# Side2.net
KiCad netlist of a schematic drawn in Altium Designer
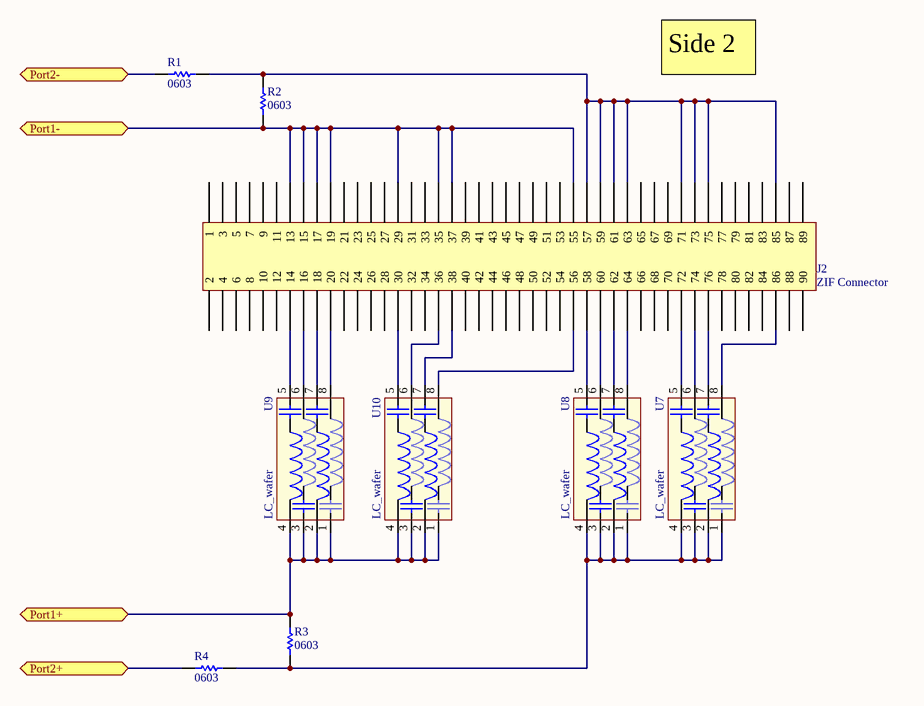
[diagram p0: Side2.SchDoc]

(export (version "E")
  (design (tool "Eeschema 10.0.6"))
  (components
    (comp (ref "J2")
      (value "ZIF Connector")
      (footprint "LCBoard_ZIFCon")
      (libsource (lib "altium-import") (part "root_1_LCboard_FH16-90S-0.3SHW(05)_"))
    )
    (comp (ref "R1")
      (value "0603")
      (footprint "0603")
      (description "RES 1 OHM 1/10W 1% 0603 SMD")
      (libsource (lib "LCboardPCB") (part "Res0603"))
    )
    (comp (ref "R2")
      (value "0603")
      (footprint "0603")
      (description "RES 1 OHM 1/10W 1% 0603 SMD")
      (libsource (lib "LCboardPCB") (part "Res0603"))
    )
    (comp (ref "R3")
      (value "0603")
      (footprint "0603")
      (description "RES 1 OHM 1/10W 1% 0603 SMD")
      (libsource (lib "LCboardPCB") (part "Res0603"))
    )
    (comp (ref "R4")
      (value "0603")
      (footprint "0603")
      (description "RES 1 OHM 1/10W 1% 0603 SMD")
      (libsource (lib "LCboardPCB") (part "Res0603"))
    )
    (comp (ref "U7")
      (value "LC_wafer")
      (footprint "LCWafer")
      (description "Gold bonded integrated LC")
      (libsource (lib "LCboardPCB") (part "LCWafer"))
    )
    (comp (ref "U8")
      (value "LC_wafer")
      (footprint "LCWafer")
      (description "Gold bonded integrated LC")
      (libsource (lib "LCboardPCB") (part "LCWafer"))
    )
    (comp (ref "U9")
      (value "LC_wafer")
      (footprint "LCWafer")
      (description "Gold bonded integrated LC")
      (libsource (lib "LCboardPCB") (part "LCWafer"))
    )
    (comp (ref "U10")
      (value "LC_wafer")
      (footprint "LCWafer")
      (description "Gold bonded integrated LC")
      (libsource (lib "LCboardPCB") (part "LCWafer"))
    )
  )
  (nets
    (net (code "1") (name "/Port1+") (class "Default")
      (node (ref "R3") (pin "2") (pinfunction "2_2") (pintype "passive"))
      (node (ref "U10") (pin "1") (pinfunction "1_1") (pintype "passive"))
      (node (ref "U10") (pin "2") (pinfunction "2_2") (pintype "passive"))
      (node (ref "U10") (pin "3") (pinfunction "3_3") (pintype "passive"))
      (node (ref "U10") (pin "4") (pinfunction "4_4") (pintype "passive"))
      (node (ref "U9") (pin "1") (pinfunction "1_1") (pintype "passive"))
      (node (ref "U9") (pin "2") (pinfunction "2_2") (pintype "passive"))
      (node (ref "U9") (pin "3") (pinfunction "3_3") (pintype "passive"))
      (node (ref "U9") (pin "4") (pinfunction "4_4") (pintype "passive"))
    )
    (net (code "2") (name "/Port1-") (class "Default")
      (node (ref "J2") (pin "13") (pinfunction "13_13") (pintype "passive"))
      (node (ref "J2") (pin "15") (pinfunction "15_15") (pintype "passive"))
      (node (ref "J2") (pin "17") (pinfunction "17_17") (pintype "passive"))
      (node (ref "J2") (pin "19") (pinfunction "19_19") (pintype "passive"))
      (node (ref "J2") (pin "29") (pinfunction "29_29") (pintype "passive"))
      (node (ref "J2") (pin "35") (pinfunction "35_35") (pintype "passive"))
      (node (ref "J2") (pin "37") (pinfunction "37_37") (pintype "passive"))
      (node (ref "J2") (pin "55") (pinfunction "55_55") (pintype "passive"))
      (node (ref "R2") (pin "1") (pinfunction "1_1") (pintype "passive"))
    )
    (net (code "3") (name "/Port2+") (class "Default")
      (node (ref "R4") (pin "2") (pinfunction "2_2") (pintype "passive"))
    )
    (net (code "4") (name "/Port2-") (class "Default")
      (node (ref "R1") (pin "2") (pinfunction "2_2") (pintype "passive"))
    )
    (net (code "5") (name "Net-(J2-Pad14)") (class "Default")
      (node (ref "J2") (pin "14") (pinfunction "14_14") (pintype "passive"))
      (node (ref "U9") (pin "5") (pinfunction "5_5") (pintype "passive"))
    )
    (net (code "6") (name "Net-(J2-Pad16)") (class "Default")
      (node (ref "J2") (pin "16") (pinfunction "16_16") (pintype "passive"))
      (node (ref "U9") (pin "6") (pinfunction "6_6") (pintype "passive"))
    )
    (net (code "7") (name "Net-(J2-Pad18)") (class "Default")
      (node (ref "J2") (pin "18") (pinfunction "18_18") (pintype "passive"))
      (node (ref "U9") (pin "7") (pinfunction "7_7") (pintype "passive"))
    )
    (net (code "8") (name "Net-(J2-Pad20)") (class "Default")
      (node (ref "J2") (pin "20") (pinfunction "20_20") (pintype "passive"))
      (node (ref "U9") (pin "8") (pinfunction "8_8") (pintype "passive"))
    )
    (net (code "9") (name "Net-(J2-Pad30)") (class "Default")
      (node (ref "J2") (pin "30") (pinfunction "30_30") (pintype "passive"))
      (node (ref "U10") (pin "5") (pinfunction "5_5") (pintype "passive"))
    )
    (net (code "10") (name "Net-(J2-Pad36)") (class "Default")
      (node (ref "J2") (pin "36") (pinfunction "36_36") (pintype "passive"))
      (node (ref "U10") (pin "6") (pinfunction "6_6") (pintype "passive"))
    )
    (net (code "11") (name "Net-(J2-Pad38)") (class "Default")
      (node (ref "J2") (pin "38") (pinfunction "38_38") (pintype "passive"))
      (node (ref "U10") (pin "7") (pinfunction "7_7") (pintype "passive"))
    )
    (net (code "12") (name "Net-(J2-Pad56)") (class "Default")
      (node (ref "J2") (pin "56") (pinfunction "56_56") (pintype "passive"))
      (node (ref "U10") (pin "8") (pinfunction "8_8") (pintype "passive"))
    )
    (net (code "13") (name "Net-(J2-Pad57)") (class "Default")
      (node (ref "J2") (pin "57") (pinfunction "57_57") (pintype "passive"))
      (node (ref "J2") (pin "59") (pinfunction "59_59") (pintype "passive"))
      (node (ref "J2") (pin "61") (pinfunction "61_61") (pintype "passive"))
      (node (ref "J2") (pin "63") (pinfunction "63_63") (pintype "passive"))
      (node (ref "J2") (pin "71") (pinfunction "71_71") (pintype "passive"))
      (node (ref "J2") (pin "73") (pinfunction "73_73") (pintype "passive"))
      (node (ref "J2") (pin "75") (pinfunction "75_75") (pintype "passive"))
      (node (ref "J2") (pin "85") (pinfunction "85_85") (pintype "passive"))
      (node (ref "R1") (pin "1") (pinfunction "1_1") (pintype "passive"))
      (node (ref "R2") (pin "2") (pinfunction "2_2") (pintype "passive"))
    )
    (net (code "14") (name "Net-(J2-Pad58)") (class "Default")
      (node (ref "J2") (pin "58") (pinfunction "58_58") (pintype "passive"))
      (node (ref "U8") (pin "5") (pinfunction "5_5") (pintype "passive"))
    )
    (net (code "15") (name "Net-(J2-Pad60)") (class "Default")
      (node (ref "J2") (pin "60") (pinfunction "60_60") (pintype "passive"))
      (node (ref "U8") (pin "6") (pinfunction "6_6") (pintype "passive"))
    )
    (net (code "16") (name "Net-(J2-Pad62)") (class "Default")
      (node (ref "J2") (pin "62") (pinfunction "62_62") (pintype "passive"))
      (node (ref "U8") (pin "7") (pinfunction "7_7") (pintype "passive"))
    )
    (net (code "17") (name "Net-(J2-Pad64)") (class "Default")
      (node (ref "J2") (pin "64") (pinfunction "64_64") (pintype "passive"))
      (node (ref "U8") (pin "8") (pinfunction "8_8") (pintype "passive"))
    )
    (net (code "18") (name "Net-(J2-Pad72)") (class "Default")
      (node (ref "J2") (pin "72") (pinfunction "72_72") (pintype "passive"))
      (node (ref "U7") (pin "5") (pinfunction "5_5") (pintype "passive"))
    )
    (net (code "19") (name "Net-(J2-Pad74)") (class "Default")
      (node (ref "J2") (pin "74") (pinfunction "74_74") (pintype "passive"))
      (node (ref "U7") (pin "6") (pinfunction "6_6") (pintype "passive"))
    )
    (net (code "20") (name "Net-(J2-Pad76)") (class "Default")
      (node (ref "J2") (pin "76") (pinfunction "76_76") (pintype "passive"))
      (node (ref "U7") (pin "7") (pinfunction "7_7") (pintype "passive"))
    )
    (net (code "21") (name "Net-(J2-Pad86)") (class "Default")
      (node (ref "J2") (pin "86") (pinfunction "86_86") (pintype "passive"))
      (node (ref "U7") (pin "8") (pinfunction "8_8") (pintype "passive"))
    )
    (net (code "22") (name "Net-(R3-Pad1)") (class "Default")
      (node (ref "R3") (pin "1") (pinfunction "1_1") (pintype "passive"))
      (node (ref "R4") (pin "1") (pinfunction "1_1") (pintype "passive"))
      (node (ref "U7") (pin "1") (pinfunction "1_1") (pintype "passive"))
      (node (ref "U7") (pin "2") (pinfunction "2_2") (pintype "passive"))
      (node (ref "U7") (pin "3") (pinfunction "3_3") (pintype "passive"))
      (node (ref "U7") (pin "4") (pinfunction "4_4") (pintype "passive"))
      (node (ref "U8") (pin "1") (pinfunction "1_1") (pintype "passive"))
      (node (ref "U8") (pin "2") (pinfunction "2_2") (pintype "passive"))
      (node (ref "U8") (pin "3") (pinfunction "3_3") (pintype "passive"))
      (node (ref "U8") (pin "4") (pinfunction "4_4") (pintype "passive"))
    )
    (net (code "23") (name "unconnected-(J2-Pad1)") (class "Default")
      (node (ref "J2") (pin "1") (pinfunction "1_1") (pintype "passive"))
    )
    (net (code "24") (name "unconnected-(J2-Pad2)") (class "Default")
      (node (ref "J2") (pin "2") (pinfunction "2_2") (pintype "passive"))
    )
    (net (code "25") (name "unconnected-(J2-Pad3)") (class "Default")
      (node (ref "J2") (pin "3") (pinfunction "3_3") (pintype "passive"))
    )
    (net (code "26") (name "unconnected-(J2-Pad4)") (class "Default")
      (node (ref "J2") (pin "4") (pinfunction "4_4") (pintype "passive"))
    )
    (net (code "27") (name "unconnected-(J2-Pad5)") (class "Default")
      (node (ref "J2") (pin "5") (pinfunction "5_5") (pintype "passive"))
    )
    (net (code "28") (name "unconnected-(J2-Pad6)") (class "Default")
      (node (ref "J2") (pin "6") (pinfunction "6_6") (pintype "passive"))
    )
    (net (code "29") (name "unconnected-(J2-Pad7)") (class "Default")
      (node (ref "J2") (pin "7") (pinfunction "7_7") (pintype "passive"))
    )
    (net (code "30") (name "unconnected-(J2-Pad8)") (class "Default")
      (node (ref "J2") (pin "8") (pinfunction "8_8") (pintype "passive"))
    )
    (net (code "31") (name "unconnected-(J2-Pad9)") (class "Default")
      (node (ref "J2") (pin "9") (pinfunction "9_9") (pintype "passive"))
    )
    (net (code "32") (name "unconnected-(J2-Pad10)") (class "Default")
      (node (ref "J2") (pin "10") (pinfunction "10_10") (pintype "passive"))
    )
    (net (code "33") (name "unconnected-(J2-Pad11)") (class "Default")
      (node (ref "J2") (pin "11") (pinfunction "11_11") (pintype "passive"))
    )
    (net (code "34") (name "unconnected-(J2-Pad12)") (class "Default")
      (node (ref "J2") (pin "12") (pinfunction "12_12") (pintype "passive"))
    )
    (net (code "35") (name "unconnected-(J2-Pad21)") (class "Default")
      (node (ref "J2") (pin "21") (pinfunction "21_21") (pintype "passive"))
    )
    (net (code "36") (name "unconnected-(J2-Pad22)") (class "Default")
      (node (ref "J2") (pin "22") (pinfunction "22_22") (pintype "passive"))
    )
    (net (code "37") (name "unconnected-(J2-Pad23)") (class "Default")
      (node (ref "J2") (pin "23") (pinfunction "23_23") (pintype "passive"))
    )
    (net (code "38") (name "unconnected-(J2-Pad24)") (class "Default")
      (node (ref "J2") (pin "24") (pinfunction "24_24") (pintype "passive"))
    )
    (net (code "39") (name "unconnected-(J2-Pad25)") (class "Default")
      (node (ref "J2") (pin "25") (pinfunction "25_25") (pintype "passive"))
    )
    (net (code "40") (name "unconnected-(J2-Pad26)") (class "Default")
      (node (ref "J2") (pin "26") (pinfunction "26_26") (pintype "passive"))
    )
    (net (code "41") (name "unconnected-(J2-Pad27)") (class "Default")
      (node (ref "J2") (pin "27") (pinfunction "27_27") (pintype "passive"))
    )
    (net (code "42") (name "unconnected-(J2-Pad28)") (class "Default")
      (node (ref "J2") (pin "28") (pinfunction "28_28") (pintype "passive"))
    )
    (net (code "43") (name "unconnected-(J2-Pad31)") (class "Default")
      (node (ref "J2") (pin "31") (pinfunction "31_31") (pintype "passive"))
    )
    (net (code "44") (name "unconnected-(J2-Pad32)") (class "Default")
      (node (ref "J2") (pin "32") (pinfunction "32_32") (pintype "passive"))
    )
    (net (code "45") (name "unconnected-(J2-Pad33)") (class "Default")
      (node (ref "J2") (pin "33") (pinfunction "33_33") (pintype "passive"))
    )
    (net (code "46") (name "unconnected-(J2-Pad34)") (class "Default")
      (node (ref "J2") (pin "34") (pinfunction "34_34") (pintype "passive"))
    )
    (net (code "47") (name "unconnected-(J2-Pad39)") (class "Default")
      (node (ref "J2") (pin "39") (pinfunction "39_39") (pintype "passive"))
    )
    (net (code "48") (name "unconnected-(J2-Pad40)") (class "Default")
      (node (ref "J2") (pin "40") (pinfunction "40_40") (pintype "passive"))
    )
    (net (code "49") (name "unconnected-(J2-Pad41)") (class "Default")
      (node (ref "J2") (pin "41") (pinfunction "41_41") (pintype "passive"))
    )
    (net (code "50") (name "unconnected-(J2-Pad42)") (class "Default")
      (node (ref "J2") (pin "42") (pinfunction "42_42") (pintype "passive"))
    )
    (net (code "51") (name "unconnected-(J2-Pad43)") (class "Default")
      (node (ref "J2") (pin "43") (pinfunction "43_43") (pintype "passive"))
    )
    (net (code "52") (name "unconnected-(J2-Pad44)") (class "Default")
      (node (ref "J2") (pin "44") (pinfunction "44_44") (pintype "passive"))
    )
    (net (code "53") (name "unconnected-(J2-Pad45)") (class "Default")
      (node (ref "J2") (pin "45") (pinfunction "45_45") (pintype "passive"))
    )
    (net (code "54") (name "unconnected-(J2-Pad46)") (class "Default")
      (node (ref "J2") (pin "46") (pinfunction "46_46") (pintype "passive"))
    )
    (net (code "55") (name "unconnected-(J2-Pad47)") (class "Default")
      (node (ref "J2") (pin "47") (pinfunction "47_47") (pintype "passive"))
    )
    (net (code "56") (name "unconnected-(J2-Pad48)") (class "Default")
      (node (ref "J2") (pin "48") (pinfunction "48_48") (pintype "passive"))
    )
    (net (code "57") (name "unconnected-(J2-Pad49)") (class "Default")
      (node (ref "J2") (pin "49") (pinfunction "49_49") (pintype "passive"))
    )
    (net (code "58") (name "unconnected-(J2-Pad50)") (class "Default")
      (node (ref "J2") (pin "50") (pinfunction "50_50") (pintype "passive"))
    )
    (net (code "59") (name "unconnected-(J2-Pad51)") (class "Default")
      (node (ref "J2") (pin "51") (pinfunction "51_51") (pintype "passive"))
    )
    (net (code "60") (name "unconnected-(J2-Pad52)") (class "Default")
      (node (ref "J2") (pin "52") (pinfunction "52_52") (pintype "passive"))
    )
    (net (code "61") (name "unconnected-(J2-Pad53)") (class "Default")
      (node (ref "J2") (pin "53") (pinfunction "53_53") (pintype "passive"))
    )
    (net (code "62") (name "unconnected-(J2-Pad54)") (class "Default")
      (node (ref "J2") (pin "54") (pinfunction "54_54") (pintype "passive"))
    )
    (net (code "63") (name "unconnected-(J2-Pad65)") (class "Default")
      (node (ref "J2") (pin "65") (pinfunction "65_65") (pintype "passive"))
    )
    (net (code "64") (name "unconnected-(J2-Pad66)") (class "Default")
      (node (ref "J2") (pin "66") (pinfunction "66_66") (pintype "passive"))
    )
    (net (code "65") (name "unconnected-(J2-Pad67)") (class "Default")
      (node (ref "J2") (pin "67") (pinfunction "67_67") (pintype "passive"))
    )
    (net (code "66") (name "unconnected-(J2-Pad68)") (class "Default")
      (node (ref "J2") (pin "68") (pinfunction "68_68") (pintype "passive"))
    )
    (net (code "67") (name "unconnected-(J2-Pad69)") (class "Default")
      (node (ref "J2") (pin "69") (pinfunction "69_69") (pintype "passive"))
    )
    (net (code "68") (name "unconnected-(J2-Pad70)") (class "Default")
      (node (ref "J2") (pin "70") (pinfunction "70_70") (pintype "passive"))
    )
    (net (code "69") (name "unconnected-(J2-Pad77)") (class "Default")
      (node (ref "J2") (pin "77") (pinfunction "77_77") (pintype "passive"))
    )
    (net (code "70") (name "unconnected-(J2-Pad78)") (class "Default")
      (node (ref "J2") (pin "78") (pinfunction "78_78") (pintype "passive"))
    )
    (net (code "71") (name "unconnected-(J2-Pad79)") (class "Default")
      (node (ref "J2") (pin "79") (pinfunction "79_79") (pintype "passive"))
    )
    (net (code "72") (name "unconnected-(J2-Pad80)") (class "Default")
      (node (ref "J2") (pin "80") (pinfunction "80_80") (pintype "passive"))
    )
    (net (code "73") (name "unconnected-(J2-Pad81)") (class "Default")
      (node (ref "J2") (pin "81") (pinfunction "81_81") (pintype "passive"))
    )
    (net (code "74") (name "unconnected-(J2-Pad82)") (class "Default")
      (node (ref "J2") (pin "82") (pinfunction "82_82") (pintype "passive"))
    )
    (net (code "75") (name "unconnected-(J2-Pad83)") (class "Default")
      (node (ref "J2") (pin "83") (pinfunction "83_83") (pintype "passive"))
    )
    (net (code "76") (name "unconnected-(J2-Pad84)") (class "Default")
      (node (ref "J2") (pin "84") (pinfunction "84_84") (pintype "passive"))
    )
    (net (code "77") (name "unconnected-(J2-Pad87)") (class "Default")
      (node (ref "J2") (pin "87") (pinfunction "87_87") (pintype "passive"))
    )
    (net (code "78") (name "unconnected-(J2-Pad88)") (class "Default")
      (node (ref "J2") (pin "88") (pinfunction "88_88") (pintype "passive"))
    )
    (net (code "79") (name "unconnected-(J2-Pad89)") (class "Default")
      (node (ref "J2") (pin "89") (pinfunction "89_89") (pintype "passive"))
    )
    (net (code "80") (name "unconnected-(J2-Pad90)") (class "Default")
      (node (ref "J2") (pin "90") (pinfunction "90_90") (pintype "passive"))
    )
  )
)
